# UART.net
KiCad netlist of a schematic drawn in Altium Designer
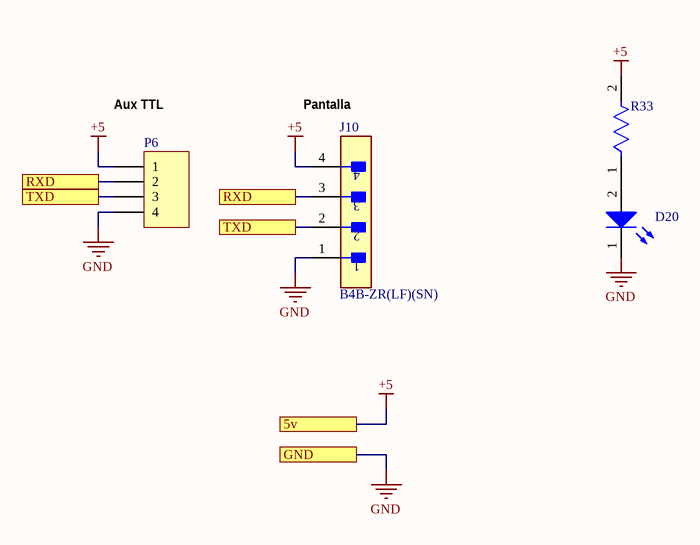
[diagram p0: UART.SchDoc]

(export (version "E")
  (design (tool "Eeschema 10.0.6"))
  (components
    (comp (ref "D20")
      (value "150080BS75000")
      (footprint "WL-SMCW_0805_150080xx75000")
      (libsource (lib "Altium Content Vault") (part "LED_Blue_2A-1K"))
    )
    (comp (ref "J10")
      (value "B4B-ZR(LF)(SN)")
      (footprint "FP-B4B-ZR_LF_SN-MFG")
      (description "CONN HEADER VERT 4POS 1.5MM")
      (libsource (lib "Altium Content Vault") (part "299a8cea1bdcbc3624fe62c390fa72c"))
    )
    (comp (ref "P6")
      (value "Header 4")
      (footprint "HDR1X4")
      (description "Header, 4-Pin")
      (fields (field (name "PUBLISHER") "Altium Limited"))
      (libsource (lib "Miscellaneous Connectors") (part "Header 4"))
    )
    (comp (ref "R33")
      (value "ERJ-P06F1001V")
      (footprint "FP-ERJP06-IPC_C")
      (description "RES SMD 1K OHM 1% 1/2W 0805")
      (fields (field (name "TOLERANCE") "1%"))
      (libsource (lib "Altium Content Vault") (part "1029c3af85768c4190bb7ad29bc67b5"))
    )
  )
  (nets
    (net (code "1") (name "+5") (class "Default")
      (node (ref "J10") (pin "4") (pinfunction "4_4") (pintype "passive"))
      (node (ref "P6") (pin "1") (pinfunction "1_1") (pintype "passive"))
      (node (ref "R33") (pin "2") (pinfunction "2_2") (pintype "passive"))
    )
    (net (code "2") (name "/RXD") (class "Default")
      (node (ref "J10") (pin "3") (pinfunction "3_3") (pintype "passive"))
      (node (ref "P6") (pin "2") (pinfunction "2_2") (pintype "passive"))
    )
    (net (code "3") (name "/TXD") (class "Default")
      (node (ref "J10") (pin "2") (pinfunction "2_2") (pintype "passive"))
      (node (ref "P6") (pin "3") (pinfunction "3_3") (pintype "passive"))
    )
    (net (code "4") (name "GND") (class "Default")
      (node (ref "D20") (pin "1") (pinfunction "K_1") (pintype "passive"))
      (node (ref "J10") (pin "1") (pinfunction "1_1") (pintype "passive"))
      (node (ref "P6") (pin "4") (pinfunction "4_4") (pintype "passive"))
    )
    (net (code "5") (name "Net-(D20-A)") (class "Default")
      (node (ref "D20") (pin "2") (pinfunction "A_2") (pintype "passive"))
      (node (ref "R33") (pin "1") (pinfunction "1_1") (pintype "passive"))
    )
  )
)
